# blinker_schematic.net
KiCad netlist of a schematic drawn in EAGLE
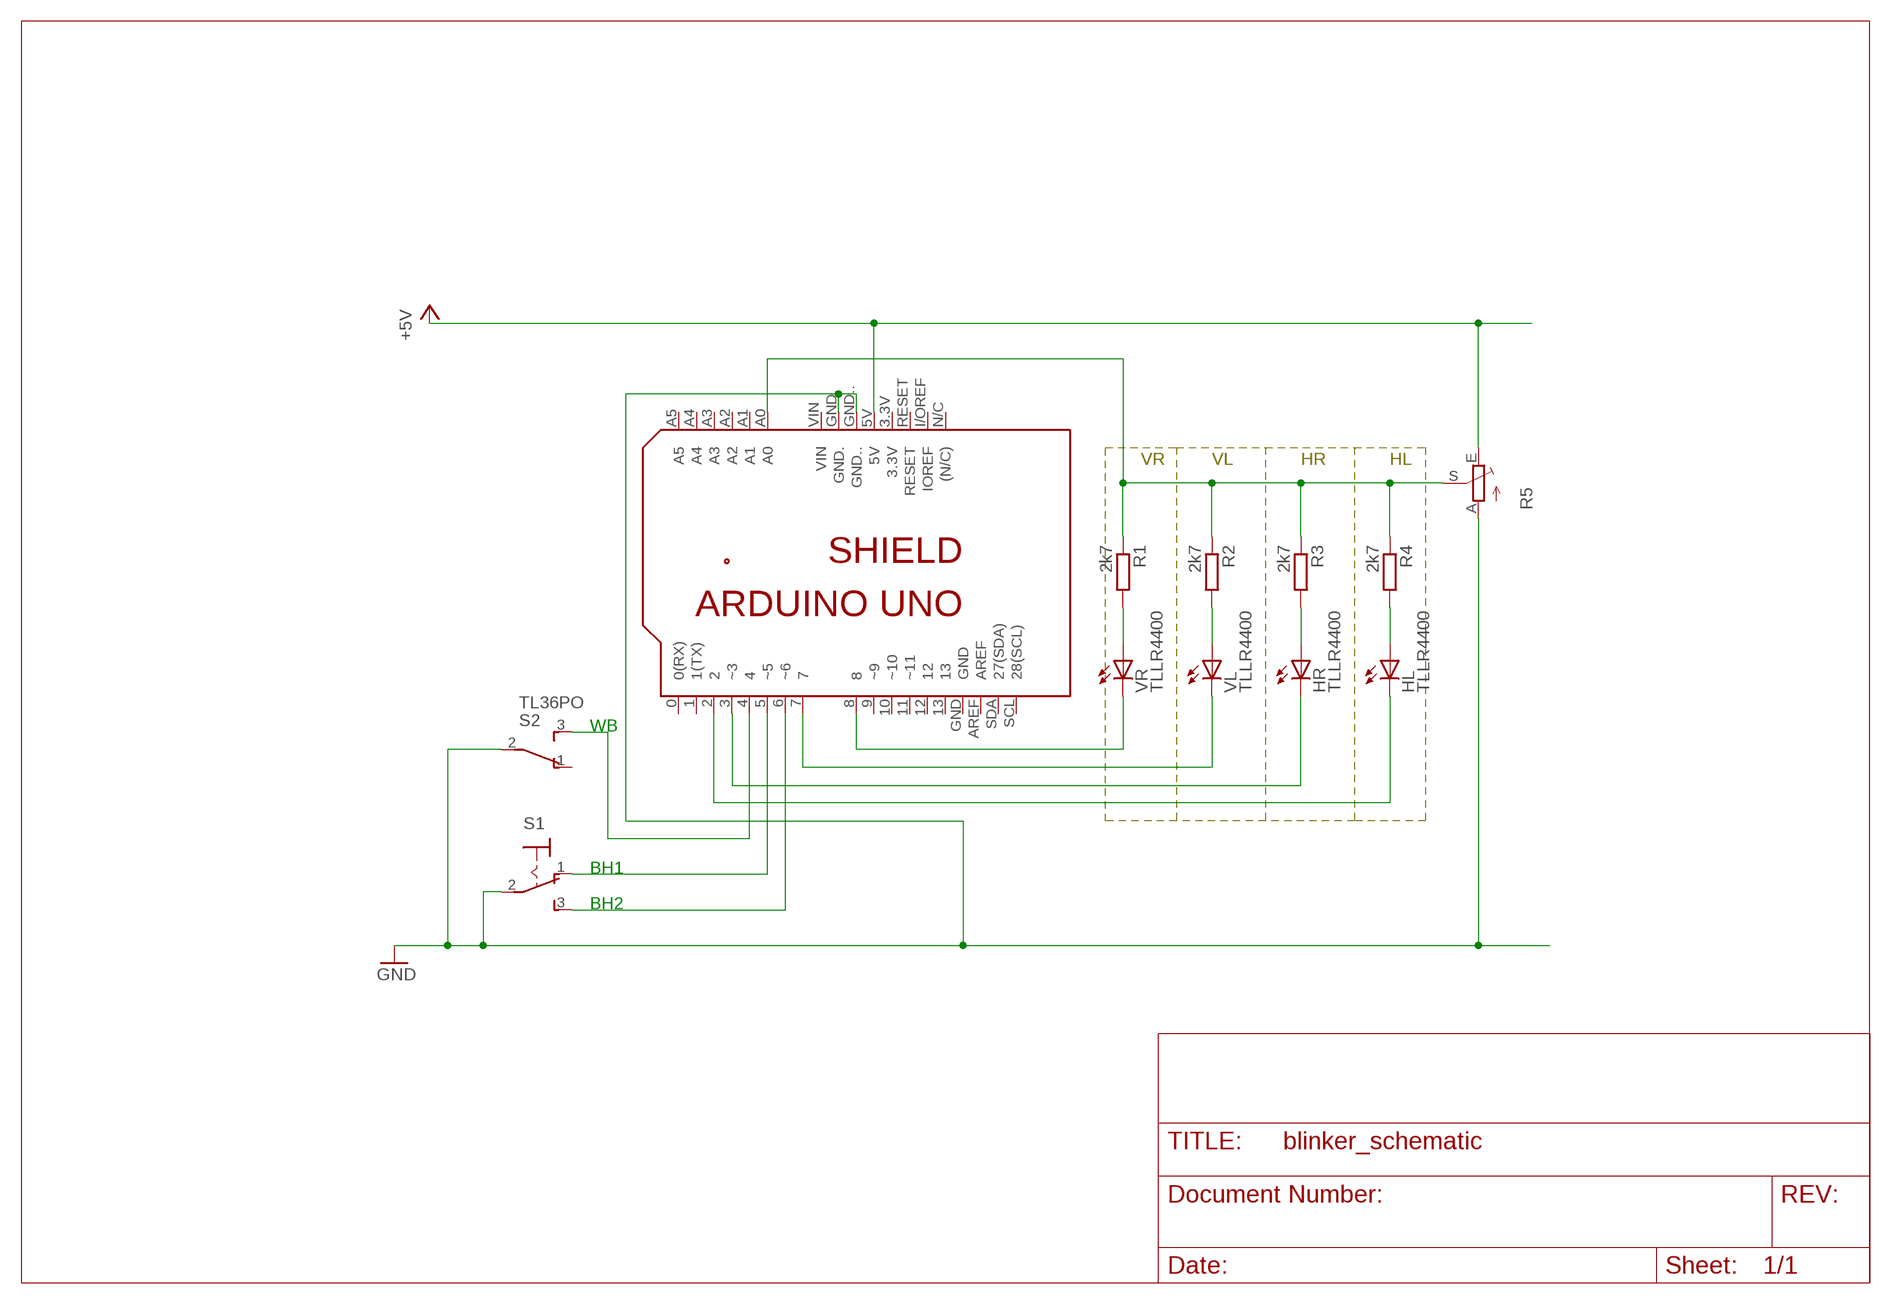
[diagram p0: schematic, sheet 1]

(export (version "E")
  (design (tool "Eeschema 10.0.6"))
  (components
    (comp (ref "HL")
      (value "TLLR4400")
      (footprint "eagle-import:LED3MM")
      (fields (field (name "MF") "VISHAY SEMICONDUCTOR"))
      (libsource (lib "eagle-import") (part "TLLR4400"))
    )
    (comp (ref "HR")
      (value "TLLR4400")
      (footprint "eagle-import:LED3MM")
      (fields (field (name "MF") "VISHAY SEMICONDUCTOR"))
      (libsource (lib "eagle-import") (part "TLLR4400"))
    )
    (comp (ref "PCB1")
      (value "ARDUINO_UNO")
      (footprint "eagle-import:ARDUINO_UNO")
      (libsource (lib "eagle-import") (part "ARDUINO_UNO"))
    )
    (comp (ref "R1")
      (value "2k7")
      (footprint "eagle-import:0207_12")
      (libsource (lib "eagle-import") (part "R-EU_0207/12"))
    )
    (comp (ref "R2")
      (value "2k7")
      (footprint "eagle-import:0207_12")
      (libsource (lib "eagle-import") (part "R-EU_0207/12"))
    )
    (comp (ref "R3")
      (value "2k7")
      (footprint "eagle-import:0207_12")
      (libsource (lib "eagle-import") (part "R-EU_0207/12"))
    )
    (comp (ref "R4")
      (value "2k7")
      (footprint "eagle-import:0207_12")
      (libsource (lib "eagle-import") (part "R-EU_0207/12"))
    )
    (comp (ref "R5")
      (value "TRIM_EU-RS3")
      (footprint "eagle-import:RS3")
      (libsource (lib "eagle-import") (part "TRIM_EU-RS3"))
    )
    (comp (ref "S1")
      (value "M9040P")
      (footprint "eagle-import:M9040P")
      (libsource (lib "eagle-import") (part "M9040P"))
    )
    (comp (ref "S2")
      (value "TL36PO")
      (footprint "eagle-import:TL3XPO")
      (libsource (lib "eagle-import") (part "TL36PO"))
    )
    (comp (ref "VL")
      (value "TLLR4400")
      (footprint "eagle-import:LED3MM")
      (fields (field (name "MF") "VISHAY SEMICONDUCTOR"))
      (libsource (lib "eagle-import") (part "TLLR4400"))
    )
    (comp (ref "VR")
      (value "TLLR4400")
      (footprint "eagle-import:LED3MM")
      (fields (field (name "MF") "VISHAY SEMICONDUCTOR"))
      (libsource (lib "eagle-import") (part "TLLR4400"))
    )
  )
  (nets
    (net (code "1") (name "+5V") (class "Default")
      (node (ref "PCB1") (pin "5V") (pinfunction "5V_5V") (pintype "bidirectional"))
      (node (ref "R5") (pin "E") (pinfunction "E_E") (pintype "passive"))
    )
    (net (code "2") (name "GND") (class "Default")
      (node (ref "PCB1") (pin "GND.") (pinfunction "GND._GND.") (pintype "bidirectional"))
      (node (ref "PCB1") (pin "GND..") (pinfunction "GND.._GND..") (pintype "bidirectional"))
      (node (ref "R5") (pin "A") (pinfunction "A_A") (pintype "passive"))
      (node (ref "S1") (pin "2") (pinfunction "P_2") (pintype "passive"))
      (node (ref "S2") (pin "2") (pinfunction "P_2") (pintype "passive"))
    )
    (net (code "3") (name "Net-(HL-C)") (class "Default")
      (node (ref "HL") (pin "K") (pinfunction "C_K") (pintype "passive"))
      (node (ref "PCB1") (pin "2") (pinfunction "2_2") (pintype "bidirectional"))
    )
    (net (code "4") (name "Net-(HL-PadA)") (class "Default")
      (node (ref "HL") (pin "A") (pinfunction "A_A") (pintype "passive"))
      (node (ref "R4") (pin "2") (pinfunction "2_2") (pintype "passive"))
    )
    (net (code "5") (name "Net-(HR-C)") (class "Default")
      (node (ref "HR") (pin "K") (pinfunction "C_K") (pintype "passive"))
      (node (ref "PCB1") (pin "3") (pinfunction "~{3}_3") (pintype "bidirectional"))
    )
    (net (code "6") (name "Net-(HR-PadA)") (class "Default")
      (node (ref "HR") (pin "A") (pinfunction "A_A") (pintype "passive"))
      (node (ref "R3") (pin "2") (pinfunction "2_2") (pintype "passive"))
    )
    (net (code "7") (name "Net-(PCB1-PadA0)") (class "Default")
      (node (ref "PCB1") (pin "A0") (pinfunction "A0_A0") (pintype "bidirectional"))
      (node (ref "R1") (pin "1") (pinfunction "1_1") (pintype "passive"))
      (node (ref "R2") (pin "1") (pinfunction "1_1") (pintype "passive"))
      (node (ref "R3") (pin "1") (pinfunction "1_1") (pintype "passive"))
      (node (ref "R4") (pin "1") (pinfunction "1_1") (pintype "passive"))
      (node (ref "R5") (pin "S") (pinfunction "S_S") (pintype "passive"))
    )
    (net (code "8") (name "Net-(PCB1-~{5})") (class "Default")
      (node (ref "PCB1") (pin "5") (pinfunction "~{5}_5") (pintype "bidirectional"))
      (node (ref "S1") (pin "1") (pinfunction "O_1") (pintype "passive"))
    )
    (net (code "9") (name "Net-(PCB1-~{6})") (class "Default")
      (node (ref "PCB1") (pin "6") (pinfunction "~{6}_6") (pintype "bidirectional"))
      (node (ref "S1") (pin "3") (pinfunction "S_3") (pintype "passive"))
    )
    (net (code "10") (name "Net-(R1-Pad2)") (class "Default")
      (node (ref "R1") (pin "2") (pinfunction "2_2") (pintype "passive"))
      (node (ref "VR") (pin "A") (pinfunction "A_A") (pintype "passive"))
    )
    (net (code "11") (name "Net-(R2-Pad2)") (class "Default")
      (node (ref "R2") (pin "2") (pinfunction "2_2") (pintype "passive"))
      (node (ref "VL") (pin "A") (pinfunction "A_A") (pintype "passive"))
    )
    (net (code "12") (name "Net-(S2-S)") (class "Default")
      (node (ref "PCB1") (pin "4") (pinfunction "4_4") (pintype "bidirectional"))
      (node (ref "S2") (pin "3") (pinfunction "S_3") (pintype "passive"))
    )
    (net (code "13") (name "Net-(VL-C)") (class "Default")
      (node (ref "PCB1") (pin "7") (pinfunction "7_7") (pintype "bidirectional"))
      (node (ref "VL") (pin "K") (pinfunction "C_K") (pintype "passive"))
    )
    (net (code "14") (name "Net-(VR-C)") (class "Default")
      (node (ref "PCB1") (pin "8") (pinfunction "8_8") (pintype "bidirectional"))
      (node (ref "VR") (pin "K") (pinfunction "C_K") (pintype "passive"))
    )
    (net (code "15") (name "unconnected-(PCB1-(N{slash}C)-PadN{slash}C)") (class "Default")
      (node (ref "PCB1") (pin "N/C") (pinfunction "(N/C)_N/C") (pintype "bidirectional"))
    )
    (net (code "16") (name "unconnected-(PCB1-0(RX)-Pad0)") (class "Default")
      (node (ref "PCB1") (pin "0") (pinfunction "0(RX)_0") (pintype "bidirectional"))
    )
    (net (code "17") (name "unconnected-(PCB1-1(TX)-Pad1)") (class "Default")
      (node (ref "PCB1") (pin "1") (pinfunction "1(TX)_1") (pintype "bidirectional"))
    )
    (net (code "18") (name "unconnected-(PCB1-27(SDA)-PadSDA)") (class "Default")
      (node (ref "PCB1") (pin "SDA") (pinfunction "27(SDA)_SDA") (pintype "bidirectional"))
    )
    (net (code "19") (name "unconnected-(PCB1-28(SCL)-PadSCL)") (class "Default")
      (node (ref "PCB1") (pin "SCL") (pinfunction "28(SCL)_SCL") (pintype "bidirectional"))
    )
    (net (code "20") (name "unconnected-(PCB1-IOREF-PadI{slash}OREF)") (class "Default")
      (node (ref "PCB1") (pin "I/OREF") (pinfunction "IOREF_I/OREF") (pintype "bidirectional"))
    )
    (net (code "21") (name "unconnected-(PCB1-Pad3.3V)") (class "Default")
      (node (ref "PCB1") (pin "3.3V") (pinfunction "3.3V_3.3V") (pintype "bidirectional"))
    )
    (net (code "22") (name "unconnected-(PCB1-Pad12)") (class "Default")
      (node (ref "PCB1") (pin "12") (pinfunction "12_12") (pintype "bidirectional"))
    )
    (net (code "23") (name "unconnected-(PCB1-Pad13)") (class "Default")
      (node (ref "PCB1") (pin "13") (pinfunction "13_13") (pintype "bidirectional"))
    )
    (net (code "24") (name "unconnected-(PCB1-PadA1)") (class "Default")
      (node (ref "PCB1") (pin "A1") (pinfunction "A1_A1") (pintype "bidirectional"))
    )
    (net (code "25") (name "unconnected-(PCB1-PadA2)") (class "Default")
      (node (ref "PCB1") (pin "A2") (pinfunction "A2_A2") (pintype "bidirectional"))
    )
    (net (code "26") (name "unconnected-(PCB1-PadA3)") (class "Default")
      (node (ref "PCB1") (pin "A3") (pinfunction "A3_A3") (pintype "bidirectional"))
    )
    (net (code "27") (name "unconnected-(PCB1-PadA4)") (class "Default")
      (node (ref "PCB1") (pin "A4") (pinfunction "A4_A4") (pintype "bidirectional"))
    )
    (net (code "28") (name "unconnected-(PCB1-PadA5)") (class "Default")
      (node (ref "PCB1") (pin "A5") (pinfunction "A5_A5") (pintype "bidirectional"))
    )
    (net (code "29") (name "unconnected-(PCB1-PadAREF)") (class "Default")
      (node (ref "PCB1") (pin "AREF") (pinfunction "AREF_AREF") (pintype "bidirectional"))
    )
    (net (code "30") (name "unconnected-(PCB1-PadGND)") (class "Default")
      (node (ref "PCB1") (pin "GND") (pinfunction "GND_GND") (pintype "bidirectional"))
    )
    (net (code "31") (name "unconnected-(PCB1-PadRESET)") (class "Default")
      (node (ref "PCB1") (pin "RESET") (pinfunction "RESET_RESET") (pintype "bidirectional"))
    )
    (net (code "32") (name "unconnected-(PCB1-PadVIN)") (class "Default")
      (node (ref "PCB1") (pin "VIN") (pinfunction "VIN_VIN") (pintype "bidirectional"))
    )
    (net (code "33") (name "unconnected-(PCB1-~{9}-Pad9)") (class "Default")
      (node (ref "PCB1") (pin "9") (pinfunction "~{9}_9") (pintype "bidirectional"))
    )
    (net (code "34") (name "unconnected-(PCB1-~{10}-Pad10)") (class "Default")
      (node (ref "PCB1") (pin "10") (pinfunction "~{10}_10") (pintype "bidirectional"))
    )
    (net (code "35") (name "unconnected-(PCB1-~{11}-Pad11)") (class "Default")
      (node (ref "PCB1") (pin "11") (pinfunction "~{11}_11") (pintype "bidirectional"))
    )
    (net (code "36") (name "unconnected-(S2-O-Pad1)") (class "Default")
      (node (ref "S2") (pin "1") (pinfunction "O_1") (pintype "passive"))
    )
  )
)
